# masterBoard.net
KiCad netlist of a schematic drawn in EAGLE
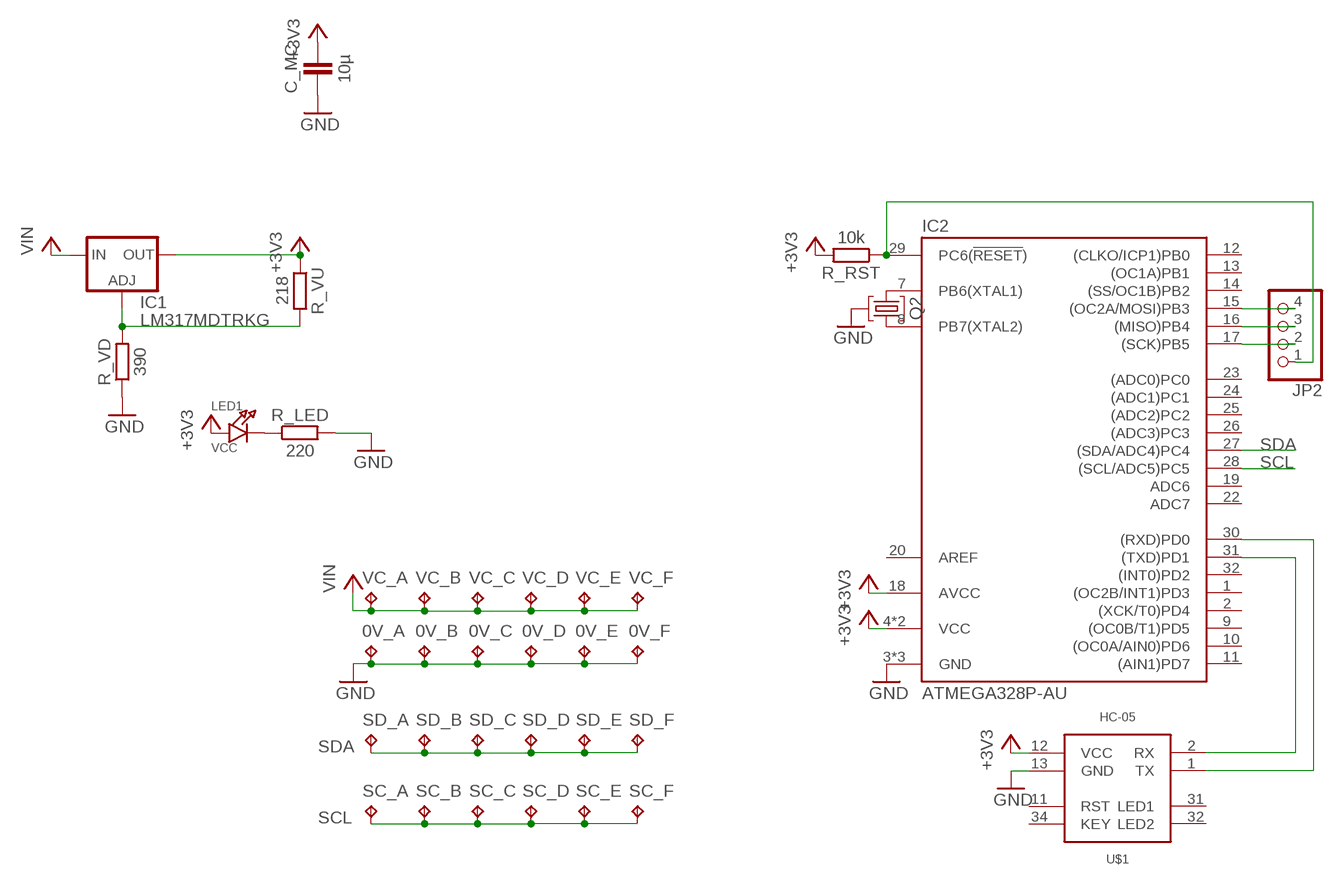
[diagram p0: schematic, sheet 1]

(export (version "E")
  (design (tool "Eeschema 10.0.6"))
  (components
    (comp (ref "0V_A")
      (value "TPTP15SQ")
      (footprint "eagle-import:TP15SQ")
      (libsource (lib "eagle-import") (part "TPTP15SQ"))
    )
    (comp (ref "0V_B")
      (value "TPTP15SQ")
      (footprint "eagle-import:TP15SQ")
      (libsource (lib "eagle-import") (part "TPTP15SQ"))
    )
    (comp (ref "0V_C")
      (value "TPTP15SQ")
      (footprint "eagle-import:TP15SQ")
      (libsource (lib "eagle-import") (part "TPTP15SQ"))
    )
    (comp (ref "0V_D")
      (value "TPTP15SQ")
      (footprint "eagle-import:TP15SQ")
      (libsource (lib "eagle-import") (part "TPTP15SQ"))
    )
    (comp (ref "0V_E")
      (value "TPTP15SQ")
      (footprint "eagle-import:TP15SQ")
      (libsource (lib "eagle-import") (part "TPTP15SQ"))
    )
    (comp (ref "0V_F")
      (value "TPTP15SQ")
      (footprint "eagle-import:TP15SQ")
      (libsource (lib "eagle-import") (part "TPTP15SQ"))
    )
    (comp (ref "C_MC")
      (value "10µ")
      (footprint "eagle-import:603")
      (libsource (lib "eagle-import") (part "CAPACITOR"))
    )
    (comp (ref "IC1")
      (value "LM317MDTRKG")
      (footprint "eagle-import:DPACK")
      (libsource (lib "eagle-import") (part "LM317?MDTRKG"))
    )
    (comp (ref "IC2")
      (value "ATMEGA328P-AU")
      (footprint "eagle-import:TQFP32")
      (libsource (lib "eagle-import") (part "ATMEGA328P-AU"))
    )
    (comp (ref "JP2")
      (value "PINHD-1X4")
      (footprint "eagle-import:1X04")
      (libsource (lib "eagle-import") (part "PINHD-1X4"))
    )
    (comp (ref "LED1")
      (value "VCC")
      (footprint "eagle-import:CHIPLED_0805")
      (libsource (lib "eagle-import") (part "LED0805"))
    )
    (comp (ref "Q2")
      (value "CRYSTAL-RES-32")
      (footprint "eagle-import:CRYSTAL_32X13")
      (libsource (lib "eagle-import") (part "CRYSTAL-RES-32"))
    )
    (comp (ref "R_LED")
      (value "220")
      (footprint "eagle-import:603")
      (libsource (lib "eagle-import") (part "RESISTOR0603"))
    )
    (comp (ref "R_RST")
      (value "10k")
      (footprint "eagle-import:603")
      (libsource (lib "eagle-import") (part "RESISTOR0603"))
    )
    (comp (ref "R_VD")
      (value "390")
      (footprint "eagle-import:603")
      (libsource (lib "eagle-import") (part "RESISTOR0603"))
    )
    (comp (ref "R_VU")
      (value "218")
      (footprint "eagle-import:603")
      (libsource (lib "eagle-import") (part "RESISTOR0603"))
    )
    (comp (ref "SC_A")
      (value "TPTP15SQ")
      (footprint "eagle-import:TP15SQ")
      (libsource (lib "eagle-import") (part "TPTP15SQ"))
    )
    (comp (ref "SC_B")
      (value "TPTP15SQ")
      (footprint "eagle-import:TP15SQ")
      (libsource (lib "eagle-import") (part "TPTP15SQ"))
    )
    (comp (ref "SC_C")
      (value "TPTP15SQ")
      (footprint "eagle-import:TP15SQ")
      (libsource (lib "eagle-import") (part "TPTP15SQ"))
    )
    (comp (ref "SC_D")
      (value "TPTP15SQ")
      (footprint "eagle-import:TP15SQ")
      (libsource (lib "eagle-import") (part "TPTP15SQ"))
    )
    (comp (ref "SC_E")
      (value "TPTP15SQ")
      (footprint "eagle-import:TP15SQ")
      (libsource (lib "eagle-import") (part "TPTP15SQ"))
    )
    (comp (ref "SC_F")
      (value "TPTP15SQ")
      (footprint "eagle-import:TP15SQ")
      (libsource (lib "eagle-import") (part "TPTP15SQ"))
    )
    (comp (ref "SD_A")
      (value "TPTP15SQ")
      (footprint "eagle-import:TP15SQ")
      (libsource (lib "eagle-import") (part "TPTP15SQ"))
    )
    (comp (ref "SD_B")
      (value "TPTP15SQ")
      (footprint "eagle-import:TP15SQ")
      (libsource (lib "eagle-import") (part "TPTP15SQ"))
    )
    (comp (ref "SD_C")
      (value "TPTP15SQ")
      (footprint "eagle-import:TP15SQ")
      (libsource (lib "eagle-import") (part "TPTP15SQ"))
    )
    (comp (ref "SD_D")
      (value "TPTP15SQ")
      (footprint "eagle-import:TP15SQ")
      (libsource (lib "eagle-import") (part "TPTP15SQ"))
    )
    (comp (ref "SD_E")
      (value "TPTP15SQ")
      (footprint "eagle-import:TP15SQ")
      (libsource (lib "eagle-import") (part "TPTP15SQ"))
    )
    (comp (ref "SD_F")
      (value "TPTP15SQ")
      (footprint "eagle-import:TP15SQ")
      (libsource (lib "eagle-import") (part "TPTP15SQ"))
    )
    (comp (ref "U$1")
      (value "HC-05")
      (footprint "eagle-import:HC-06")
      (libsource (lib "eagle-import") (part "HC-05"))
    )
    (comp (ref "VC_A")
      (value "TPTP15SQ")
      (footprint "eagle-import:TP15SQ")
      (libsource (lib "eagle-import") (part "TPTP15SQ"))
    )
    (comp (ref "VC_B")
      (value "TPTP15SQ")
      (footprint "eagle-import:TP15SQ")
      (libsource (lib "eagle-import") (part "TPTP15SQ"))
    )
    (comp (ref "VC_C")
      (value "TPTP15SQ")
      (footprint "eagle-import:TP15SQ")
      (libsource (lib "eagle-import") (part "TPTP15SQ"))
    )
    (comp (ref "VC_D")
      (value "TPTP15SQ")
      (footprint "eagle-import:TP15SQ")
      (libsource (lib "eagle-import") (part "TPTP15SQ"))
    )
    (comp (ref "VC_E")
      (value "TPTP15SQ")
      (footprint "eagle-import:TP15SQ")
      (libsource (lib "eagle-import") (part "TPTP15SQ"))
    )
    (comp (ref "VC_F")
      (value "TPTP15SQ")
      (footprint "eagle-import:TP15SQ")
      (libsource (lib "eagle-import") (part "TPTP15SQ"))
    )
  )
  (nets
    (net (code "1") (name "+3V3") (class "Default")
      (node (ref "C_MC") (pin "2") (pinfunction "2_2") (pintype "passive"))
      (node (ref "IC1") (pin "4") (pinfunction "OUT_4") (pintype "passive"))
      (node (ref "IC2") (pin "18") (pinfunction "AVCC_18") (pintype "power_in"))
      (node (ref "IC2") (pin "4") (pinfunction "VCC_4") (pintype "power_in"))
      (node (ref "IC2") (pin "6") (pinfunction "VCC_6") (pintype "power_in"))
      (node (ref "LED1") (pin "A") (pinfunction "A_A") (pintype "passive"))
      (node (ref "R_RST") (pin "2") (pinfunction "2_2") (pintype "passive"))
      (node (ref "R_VU") (pin "1") (pinfunction "1_1") (pintype "passive"))
      (node (ref "U$1") (pin "12") (pinfunction "VCC_12") (pintype "bidirectional"))
    )
    (net (code "2") (name "/SCL") (class "Default")
      (node (ref "IC2") (pin "28") (pinfunction "(SCL/ADC5)PC5_28") (pintype "bidirectional"))
      (node (ref "SC_A") (pin "TP") (pinfunction "TP_TP") (pintype "input"))
      (node (ref "SC_B") (pin "TP") (pinfunction "TP_TP") (pintype "input"))
      (node (ref "SC_C") (pin "TP") (pinfunction "TP_TP") (pintype "input"))
      (node (ref "SC_D") (pin "TP") (pinfunction "TP_TP") (pintype "input"))
      (node (ref "SC_E") (pin "TP") (pinfunction "TP_TP") (pintype "input"))
      (node (ref "SC_F") (pin "TP") (pinfunction "TP_TP") (pintype "input"))
    )
    (net (code "3") (name "/SDA") (class "Default")
      (node (ref "IC2") (pin "27") (pinfunction "(SDA/ADC4)PC4_27") (pintype "bidirectional"))
      (node (ref "SD_A") (pin "TP") (pinfunction "TP_TP") (pintype "input"))
      (node (ref "SD_B") (pin "TP") (pinfunction "TP_TP") (pintype "input"))
      (node (ref "SD_C") (pin "TP") (pinfunction "TP_TP") (pintype "input"))
      (node (ref "SD_D") (pin "TP") (pinfunction "TP_TP") (pintype "input"))
      (node (ref "SD_E") (pin "TP") (pinfunction "TP_TP") (pintype "input"))
      (node (ref "SD_F") (pin "TP") (pinfunction "TP_TP") (pintype "input"))
    )
    (net (code "4") (name "GND") (class "Default")
      (node (ref "0V_A") (pin "TP") (pinfunction "TP_TP") (pintype "input"))
      (node (ref "0V_B") (pin "TP") (pinfunction "TP_TP") (pintype "input"))
      (node (ref "0V_C") (pin "TP") (pinfunction "TP_TP") (pintype "input"))
      (node (ref "0V_D") (pin "TP") (pinfunction "TP_TP") (pintype "input"))
      (node (ref "0V_E") (pin "TP") (pinfunction "TP_TP") (pintype "input"))
      (node (ref "0V_F") (pin "TP") (pinfunction "TP_TP") (pintype "input"))
      (node (ref "C_MC") (pin "1") (pinfunction "1_1") (pintype "passive"))
      (node (ref "IC2") (pin "21") (pinfunction "GND_21") (pintype "power_in"))
      (node (ref "IC2") (pin "3") (pinfunction "GND_3") (pintype "power_in"))
      (node (ref "IC2") (pin "5") (pinfunction "GND_5") (pintype "power_in"))
      (node (ref "Q2") (pin "GND") (pinfunction "GND_GND") (pintype "passive"))
      (node (ref "R_LED") (pin "2") (pinfunction "2_2") (pintype "passive"))
      (node (ref "R_VD") (pin "1") (pinfunction "1_1") (pintype "passive"))
      (node (ref "U$1") (pin "13") (pinfunction "GND_13") (pintype "bidirectional"))
    )
    (net (code "5") (name "Net-(IC1-ADJ)") (class "Default")
      (node (ref "IC1") (pin "1") (pinfunction "ADJ_1") (pintype "input"))
      (node (ref "R_VD") (pin "2") (pinfunction "2_2") (pintype "passive"))
      (node (ref "R_VU") (pin "2") (pinfunction "2_2") (pintype "passive"))
    )
    (net (code "6") (name "Net-(IC2-(MISO)PB4)") (class "Default")
      (node (ref "IC2") (pin "16") (pinfunction "(MISO)PB4_16") (pintype "bidirectional"))
      (node (ref "JP2") (pin "3") (pinfunction "3_3") (pintype "passive"))
    )
    (net (code "7") (name "Net-(IC2-(OC2A{slash}MOSI)PB3)") (class "Default")
      (node (ref "IC2") (pin "15") (pinfunction "(OC2A/MOSI)PB3_15") (pintype "bidirectional"))
      (node (ref "JP2") (pin "4") (pinfunction "4_4") (pintype "passive"))
    )
    (net (code "8") (name "Net-(IC2-(RXD)PD0)") (class "Default")
      (node (ref "IC2") (pin "30") (pinfunction "(RXD)PD0_30") (pintype "bidirectional"))
      (node (ref "U$1") (pin "1") (pinfunction "TX_1") (pintype "bidirectional"))
    )
    (net (code "9") (name "Net-(IC2-(SCK)PB5)") (class "Default")
      (node (ref "IC2") (pin "17") (pinfunction "(SCK)PB5_17") (pintype "bidirectional"))
      (node (ref "JP2") (pin "2") (pinfunction "2_2") (pintype "passive"))
    )
    (net (code "10") (name "Net-(IC2-(TXD)PD1)") (class "Default")
      (node (ref "IC2") (pin "31") (pinfunction "(TXD)PD1_31") (pintype "bidirectional"))
      (node (ref "U$1") (pin "2") (pinfunction "RX_2") (pintype "bidirectional"))
    )
    (net (code "11") (name "Net-(IC2-PB6(XTAL1))") (class "Default")
      (node (ref "IC2") (pin "7") (pinfunction "PB6(XTAL1)_7") (pintype "bidirectional"))
      (node (ref "Q2") (pin "2") (pinfunction "2_2") (pintype "passive"))
    )
    (net (code "12") (name "Net-(IC2-PB7(XTAL2))") (class "Default")
      (node (ref "IC2") (pin "8") (pinfunction "PB7(XTAL2)_8") (pintype "bidirectional"))
      (node (ref "Q2") (pin "1") (pinfunction "1_1") (pintype "passive"))
    )
    (net (code "13") (name "Net-(IC2-PC6(~{RESET}))") (class "Default")
      (node (ref "IC2") (pin "29") (pinfunction "PC6(~{RESET})_29") (pintype "bidirectional"))
      (node (ref "JP2") (pin "1") (pinfunction "1_1") (pintype "passive"))
      (node (ref "R_RST") (pin "1") (pinfunction "1_1") (pintype "passive"))
    )
    (net (code "14") (name "Net-(LED1-PadC)") (class "Default")
      (node (ref "LED1") (pin "C") (pinfunction "C_C") (pintype "passive"))
      (node (ref "R_LED") (pin "1") (pinfunction "1_1") (pintype "passive"))
    )
    (net (code "15") (name "VIN") (class "Default")
      (node (ref "IC1") (pin "3") (pinfunction "IN_3") (pintype "input"))
      (node (ref "VC_A") (pin "TP") (pinfunction "TP_TP") (pintype "input"))
      (node (ref "VC_B") (pin "TP") (pinfunction "TP_TP") (pintype "input"))
      (node (ref "VC_C") (pin "TP") (pinfunction "TP_TP") (pintype "input"))
      (node (ref "VC_D") (pin "TP") (pinfunction "TP_TP") (pintype "input"))
      (node (ref "VC_E") (pin "TP") (pinfunction "TP_TP") (pintype "input"))
      (node (ref "VC_F") (pin "TP") (pinfunction "TP_TP") (pintype "input"))
    )
    (net (code "16") (name "unconnected-(IC2-(ADC0)PC0-Pad23)") (class "Default")
      (node (ref "IC2") (pin "23") (pinfunction "(ADC0)PC0_23") (pintype "bidirectional"))
    )
    (net (code "17") (name "unconnected-(IC2-(ADC1)PC1-Pad24)") (class "Default")
      (node (ref "IC2") (pin "24") (pinfunction "(ADC1)PC1_24") (pintype "bidirectional"))
    )
    (net (code "18") (name "unconnected-(IC2-(ADC2)PC2-Pad25)") (class "Default")
      (node (ref "IC2") (pin "25") (pinfunction "(ADC2)PC2_25") (pintype "bidirectional"))
    )
    (net (code "19") (name "unconnected-(IC2-(ADC3)PC3-Pad26)") (class "Default")
      (node (ref "IC2") (pin "26") (pinfunction "(ADC3)PC3_26") (pintype "bidirectional"))
    )
    (net (code "20") (name "unconnected-(IC2-(AIN1)PD7-Pad11)") (class "Default")
      (node (ref "IC2") (pin "11") (pinfunction "(AIN1)PD7_11") (pintype "bidirectional"))
    )
    (net (code "21") (name "unconnected-(IC2-(CLKO{slash}ICP1)PB0-Pad12)") (class "Default")
      (node (ref "IC2") (pin "12") (pinfunction "(CLKO/ICP1)PB0_12") (pintype "bidirectional"))
    )
    (net (code "22") (name "unconnected-(IC2-(INT0)PD2-Pad32)") (class "Default")
      (node (ref "IC2") (pin "32") (pinfunction "(INT0)PD2_32") (pintype "bidirectional"))
    )
    (net (code "23") (name "unconnected-(IC2-(OC0A{slash}AIN0)PD6-Pad10)") (class "Default")
      (node (ref "IC2") (pin "10") (pinfunction "(OC0A/AIN0)PD6_10") (pintype "bidirectional"))
    )
    (net (code "24") (name "unconnected-(IC2-(OC0B{slash}T1)PD5-Pad9)") (class "Default")
      (node (ref "IC2") (pin "9") (pinfunction "(OC0B/T1)PD5_9") (pintype "bidirectional"))
    )
    (net (code "25") (name "unconnected-(IC2-(OC1A)PB1-Pad13)") (class "Default")
      (node (ref "IC2") (pin "13") (pinfunction "(OC1A)PB1_13") (pintype "bidirectional"))
    )
    (net (code "26") (name "unconnected-(IC2-(OC2B{slash}INT1)PD3-Pad1)") (class "Default")
      (node (ref "IC2") (pin "1") (pinfunction "(OC2B/INT1)PD3_1") (pintype "bidirectional"))
    )
    (net (code "27") (name "unconnected-(IC2-(SS{slash}OC1B)PB2-Pad14)") (class "Default")
      (node (ref "IC2") (pin "14") (pinfunction "(SS/OC1B)PB2_14") (pintype "bidirectional"))
    )
    (net (code "28") (name "unconnected-(IC2-(XCK{slash}T0)PD4-Pad2)") (class "Default")
      (node (ref "IC2") (pin "2") (pinfunction "(XCK/T0)PD4_2") (pintype "bidirectional"))
    )
    (net (code "29") (name "unconnected-(IC2-ADC6-Pad19)") (class "Default")
      (node (ref "IC2") (pin "19") (pinfunction "ADC6_19") (pintype "bidirectional"))
    )
    (net (code "30") (name "unconnected-(IC2-ADC7-Pad22)") (class "Default")
      (node (ref "IC2") (pin "22") (pinfunction "ADC7_22") (pintype "bidirectional"))
    )
    (net (code "31") (name "unconnected-(IC2-AREF-Pad20)") (class "Default")
      (node (ref "IC2") (pin "20") (pinfunction "AREF_20") (pintype "passive"))
    )
    (net (code "32") (name "unconnected-(U$1-KEY-Pad34)") (class "Default")
      (node (ref "U$1") (pin "34") (pinfunction "KEY_34") (pintype "bidirectional"))
    )
    (net (code "33") (name "unconnected-(U$1-LED1-Pad31)") (class "Default")
      (node (ref "U$1") (pin "31") (pinfunction "LED1_31") (pintype "bidirectional"))
    )
    (net (code "34") (name "unconnected-(U$1-LED2-Pad32)") (class "Default")
      (node (ref "U$1") (pin "32") (pinfunction "LED2_32") (pintype "bidirectional"))
    )
    (net (code "35") (name "unconnected-(U$1-RST-Pad11)") (class "Default")
      (node (ref "U$1") (pin "11") (pinfunction "RST_11") (pintype "bidirectional"))
    )
  )
)
